# Sheet2.net
KiCad netlist of a schematic drawn in Altium Designer
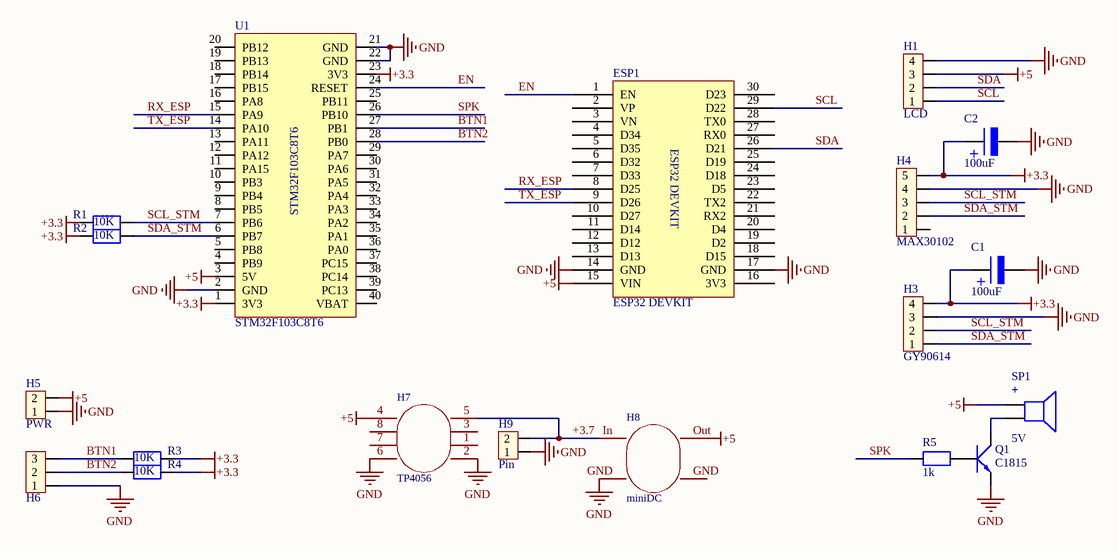
[diagram p0: Sheet2.SchDoc]

(export (version "E")
  (design (tool "Eeschema 10.0.6"))
  (components
    (comp (ref "C1")
      (value "100uF")
      (footprint "cap - 470uF/35v")
      (description "phan cuc")
      (libsource (lib "Scorer_Tran_Library") (part "Cap1"))
    )
    (comp (ref "C2")
      (value "100uF")
      (footprint "cap - 470uF/35v")
      (description "phan cuc")
      (libsource (lib "Scorer_Tran_Library") (part "Cap1"))
    )
    (comp (ref "ESP1")
      (value "ESP32 DEVKIT")
      (footprint "ESP32")
      (description "module")
      (libsource (lib "Scorer_Tran_Library") (part "ESP32"))
    )
    (comp (ref "H1")
      (value "LCD")
      (footprint "XH2.54 4P")
      (description "Header")
      (libsource (lib "SE_Altium_LIB") (part "HEADER 4P"))
    )
    (comp (ref "H3")
      (value "GY90614")
      (footprint "XH2.54 4P")
      (description "Header")
      (libsource (lib "SE_Altium_LIB") (part "HEADER 4P"))
    )
    (comp (ref "H4")
      (value "MAX30102")
      (footprint "XH2.54 5P")
      (description "Header")
      (libsource (lib "SE_Altium_LIB") (part "HEADER 5P"))
    )
    (comp (ref "H5")
      (value "PWR")
      (footprint "KF301 2P")
      (description "Header")
      (libsource (lib "SE_Altium_LIB") (part "HEADER 2P"))
    )
    (comp (ref "H6")
      (value "KF301")
      (footprint "KF301 3P")
      (description "Header")
      (libsource (lib "SE_Altium_LIB") (part "HEADER 3P"))
    )
    (comp (ref "H7")
      (value "TP4056")
      (footprint "HDR2X4")
      (fields (field (name "PUBLISHER") "Altium Limited"))
      (libsource (lib "") (part "root_0_Header 4X2__1"))
    )
    (comp (ref "H8")
      (value "miniDC")
      (footprint "HDR2X4")
      (fields (field (name "PUBLISHER") "Altium Limited"))
      (libsource (lib "altium-import") (part "root_0_Header 4X2_"))
    )
    (comp (ref "H9")
      (value "Pin")
      (footprint "KF301 2P")
      (description "Header")
      (libsource (lib "SE_Altium_LIB") (part "HEADER 2P"))
    )
    (comp (ref "Q1")
      (value "C1815")
      (footprint "NPN")
      (description "NPN")
      (libsource (lib "Scorer_Tran_Library") (part "C1815"))
    )
    (comp (ref "R1")
      (value "10K")
      (footprint "RES")
      (description "1k, 1/4W")
      (libsource (lib "Scorer_Tran_Library") (part "Resistor"))
    )
    (comp (ref "R2")
      (value "10K")
      (footprint "RES")
      (description "1k, 1/4W")
      (libsource (lib "Scorer_Tran_Library") (part "Resistor"))
    )
    (comp (ref "R3")
      (value "10K")
      (footprint "RES")
      (description "1k, 1/4W")
      (libsource (lib "Scorer_Tran_Library") (part "Resistor"))
    )
    (comp (ref "R4")
      (value "10K")
      (footprint "RES")
      (description "1k, 1/4W")
      (libsource (lib "Scorer_Tran_Library") (part "Resistor"))
    )
    (comp (ref "R5")
      (value "1k")
      (footprint "RES")
      (description "1k, 1/4W")
      (libsource (lib "Scorer_Tran_Library") (part "Resistor"))
    )
    (comp (ref "SP1")
      (value "5V")
      (footprint "Coi chip 5V")
      (description "Speaker")
      (libsource (lib "Scorer_Tran_Library") (part "Coi chip 5V"))
    )
    (comp (ref "U1")
      (value "STM32F103C8T6")
      (footprint "KIT STM32F103C8T6")
      (libsource (lib "Scorer_Tran_Library") (part "STM32"))
    )
  )
  (nets
    (net (code "1") (name "+3.3") (class "Default")
      (node (ref "C1") (pin "1") (pinfunction "VCC_1") (pintype "passive"))
      (node (ref "C2") (pin "1") (pinfunction "VCC_1") (pintype "passive"))
      (node (ref "H3") (pin "4") (pinfunction "4_4") (pintype "passive"))
      (node (ref "H4") (pin "5") (pinfunction "5_5") (pintype "passive"))
      (node (ref "R1") (pin "2") (pinfunction "2_2") (pintype "passive"))
      (node (ref "R2") (pin "2") (pinfunction "2_2") (pintype "passive"))
      (node (ref "R3") (pin "1") (pinfunction "1_1") (pintype "passive"))
      (node (ref "R4") (pin "1") (pinfunction "1_1") (pintype "passive"))
      (node (ref "U1") (pin "1") (pinfunction "3V3_1") (pintype "passive"))
      (node (ref "U1") (pin "23") (pinfunction "3V3_23") (pintype "passive"))
    )
    (net (code "2") (name "+5") (class "Default")
      (node (ref "ESP1") (pin "15") (pinfunction "VIN_15") (pintype "passive"))
      (node (ref "H1") (pin "3") (pinfunction "3_3") (pintype "passive"))
      (node (ref "H5") (pin "2") (pinfunction "2_2") (pintype "passive"))
      (node (ref "H7") (pin "4") (pinfunction "1_4") (pintype "passive"))
      (node (ref "H8") (pin "Out") (pinfunction "2_Out") (pintype "passive"))
      (node (ref "SP1") (pin "1") (pinfunction "1_1") (pintype "passive"))
      (node (ref "U1") (pin "3") (pinfunction "5V_3") (pintype "passive"))
    )
    (net (code "3") (name "/+3.7") (class "Default")
      (node (ref "H7") (pin "5") (pinfunction "2_5") (pintype "passive"))
      (node (ref "H8") (pin "In") (pinfunction "1_In") (pintype "passive"))
      (node (ref "H9") (pin "2") (pinfunction "2_2") (pintype "passive"))
    )
    (net (code "4") (name "/BTN1") (class "Default")
      (node (ref "H6") (pin "3") (pinfunction "3_3") (pintype "passive"))
      (node (ref "R3") (pin "2") (pinfunction "2_2") (pintype "passive"))
      (node (ref "U1") (pin "27") (pinfunction "PB1_27") (pintype "passive"))
    )
    (net (code "5") (name "/BTN2") (class "Default")
      (node (ref "H6") (pin "2") (pinfunction "2_2") (pintype "passive"))
      (node (ref "R4") (pin "2") (pinfunction "2_2") (pintype "passive"))
      (node (ref "U1") (pin "28") (pinfunction "PB0_28") (pintype "passive"))
    )
    (net (code "6") (name "/EN") (class "Default")
      (node (ref "ESP1") (pin "1") (pinfunction "EN_1") (pintype "passive"))
      (node (ref "U1") (pin "24") (pinfunction "RESET_24") (pintype "passive"))
    )
    (net (code "7") (name "/RX_ESP") (class "Default")
      (node (ref "ESP1") (pin "8") (pinfunction "D25_8") (pintype "passive"))
      (node (ref "U1") (pin "15") (pinfunction "PA9_15") (pintype "passive"))
    )
    (net (code "8") (name "/SCL") (class "Default")
      (node (ref "ESP1") (pin "29") (pinfunction "D22_29") (pintype "passive"))
      (node (ref "H1") (pin "1") (pinfunction "1_1") (pintype "passive"))
    )
    (net (code "9") (name "/SCL_STM") (class "Default")
      (node (ref "H3") (pin "2") (pinfunction "2_2") (pintype "passive"))
      (node (ref "H4") (pin "3") (pinfunction "3_3") (pintype "passive"))
      (node (ref "R1") (pin "1") (pinfunction "1_1") (pintype "passive"))
      (node (ref "U1") (pin "7") (pinfunction "PB6_7") (pintype "passive"))
    )
    (net (code "10") (name "/SDA") (class "Default")
      (node (ref "ESP1") (pin "26") (pinfunction "D21_26") (pintype "passive"))
      (node (ref "H1") (pin "2") (pinfunction "2_2") (pintype "passive"))
    )
    (net (code "11") (name "/SDA_STM") (class "Default")
      (node (ref "H3") (pin "1") (pinfunction "1_1") (pintype "passive"))
      (node (ref "H4") (pin "2") (pinfunction "2_2") (pintype "passive"))
      (node (ref "R2") (pin "1") (pinfunction "1_1") (pintype "passive"))
      (node (ref "U1") (pin "6") (pinfunction "PB7_6") (pintype "passive"))
    )
    (net (code "12") (name "/SPK") (class "Default")
      (node (ref "R5") (pin "2") (pinfunction "2_2") (pintype "passive"))
      (node (ref "U1") (pin "26") (pinfunction "PB10_26") (pintype "passive"))
    )
    (net (code "13") (name "/TX_ESP") (class "Default")
      (node (ref "ESP1") (pin "9") (pinfunction "D26_9") (pintype "passive"))
      (node (ref "U1") (pin "14") (pinfunction "PA10_14") (pintype "passive"))
    )
    (net (code "14") (name "GND") (class "Default")
      (node (ref "C1") (pin "2") (pinfunction "GND_2") (pintype "passive"))
      (node (ref "C2") (pin "2") (pinfunction "GND_2") (pintype "passive"))
      (node (ref "ESP1") (pin "14") (pinfunction "GND_14") (pintype "passive"))
      (node (ref "ESP1") (pin "17") (pinfunction "GND_17") (pintype "passive"))
      (node (ref "H1") (pin "4") (pinfunction "4_4") (pintype "passive"))
      (node (ref "H3") (pin "3") (pinfunction "3_3") (pintype "passive"))
      (node (ref "H4") (pin "4") (pinfunction "4_4") (pintype "passive"))
      (node (ref "H5") (pin "1") (pinfunction "1_1") (pintype "passive"))
      (node (ref "H6") (pin "1") (pinfunction "1_1") (pintype "passive"))
      (node (ref "H7") (pin "2") (pinfunction "8_2") (pintype "passive"))
      (node (ref "H7") (pin "6") (pinfunction "7_6") (pintype "passive"))
      (node (ref "H8") (pin "GND") (pinfunction "7_GND") (pintype "passive"))
      (node (ref "H9") (pin "1") (pinfunction "1_1") (pintype "passive"))
      (node (ref "Q1") (pin "1") (pinfunction "E_1") (pintype "passive"))
      (node (ref "U1") (pin "2") (pinfunction "GND_2") (pintype "passive"))
      (node (ref "U1") (pin "21") (pinfunction "GND_21") (pintype "passive"))
      (node (ref "U1") (pin "22") (pinfunction "GND_22") (pintype "passive"))
    )
    (net (code "15") (name "Net-(Q1-B)") (class "Default")
      (node (ref "Q1") (pin "3") (pinfunction "B_3") (pintype "passive"))
      (node (ref "R5") (pin "1") (pinfunction "1_1") (pintype "passive"))
    )
    (net (code "16") (name "Net-(Q1-C)") (class "Default")
      (node (ref "Q1") (pin "2") (pinfunction "C_2") (pintype "passive"))
      (node (ref "SP1") (pin "2") (pinfunction "2_2") (pintype "passive"))
    )
    (net (code "17") (name "unconnected-(ESP1-3V3-Pad16)") (class "Default")
      (node (ref "ESP1") (pin "16") (pinfunction "3V3_16") (pintype "passive"))
    )
    (net (code "18") (name "unconnected-(ESP1-D2-Pad19)") (class "Default")
      (node (ref "ESP1") (pin "19") (pinfunction "D2_19") (pintype "passive"))
    )
    (net (code "19") (name "unconnected-(ESP1-D4-Pad20)") (class "Default")
      (node (ref "ESP1") (pin "20") (pinfunction "D4_20") (pintype "passive"))
    )
    (net (code "20") (name "unconnected-(ESP1-D5-Pad23)") (class "Default")
      (node (ref "ESP1") (pin "23") (pinfunction "D5_23") (pintype "passive"))
    )
    (net (code "21") (name "unconnected-(ESP1-D12-Pad12)") (class "Default")
      (node (ref "ESP1") (pin "12") (pinfunction "D12_12") (pintype "passive"))
    )
    (net (code "22") (name "unconnected-(ESP1-D13-Pad13)") (class "Default")
      (node (ref "ESP1") (pin "13") (pinfunction "D13_13") (pintype "passive"))
    )
    (net (code "23") (name "unconnected-(ESP1-D14-Pad11)") (class "Default")
      (node (ref "ESP1") (pin "11") (pinfunction "D14_11") (pintype "passive"))
    )
    (net (code "24") (name "unconnected-(ESP1-D15-Pad18)") (class "Default")
      (node (ref "ESP1") (pin "18") (pinfunction "D15_18") (pintype "passive"))
    )
    (net (code "25") (name "unconnected-(ESP1-D18-Pad24)") (class "Default")
      (node (ref "ESP1") (pin "24") (pinfunction "D18_24") (pintype "passive"))
    )
    (net (code "26") (name "unconnected-(ESP1-D19-Pad25)") (class "Default")
      (node (ref "ESP1") (pin "25") (pinfunction "D19_25") (pintype "passive"))
    )
    (net (code "27") (name "unconnected-(ESP1-D23-Pad30)") (class "Default")
      (node (ref "ESP1") (pin "30") (pinfunction "D23_30") (pintype "passive"))
    )
    (net (code "28") (name "unconnected-(ESP1-D27-Pad10)") (class "Default")
      (node (ref "ESP1") (pin "10") (pinfunction "D27_10") (pintype "passive"))
    )
    (net (code "29") (name "unconnected-(ESP1-D32-Pad6)") (class "Default")
      (node (ref "ESP1") (pin "6") (pinfunction "D32_6") (pintype "passive"))
    )
    (net (code "30") (name "unconnected-(ESP1-D33-Pad7)") (class "Default")
      (node (ref "ESP1") (pin "7") (pinfunction "D33_7") (pintype "passive"))
    )
    (net (code "31") (name "unconnected-(ESP1-D34-Pad4)") (class "Default")
      (node (ref "ESP1") (pin "4") (pinfunction "D34_4") (pintype "passive"))
    )
    (net (code "32") (name "unconnected-(ESP1-D35-Pad5)") (class "Default")
      (node (ref "ESP1") (pin "5") (pinfunction "D35_5") (pintype "passive"))
    )
    (net (code "33") (name "unconnected-(ESP1-RX0-Pad27)") (class "Default")
      (node (ref "ESP1") (pin "27") (pinfunction "RX0_27") (pintype "passive"))
    )
    (net (code "34") (name "unconnected-(ESP1-RX2-Pad21)") (class "Default")
      (node (ref "ESP1") (pin "21") (pinfunction "RX2_21") (pintype "passive"))
    )
    (net (code "35") (name "unconnected-(ESP1-TX0-Pad28)") (class "Default")
      (node (ref "ESP1") (pin "28") (pinfunction "TX0_28") (pintype "passive"))
    )
    (net (code "36") (name "unconnected-(ESP1-TX2-Pad22)") (class "Default")
      (node (ref "ESP1") (pin "22") (pinfunction "TX2_22") (pintype "passive"))
    )
    (net (code "37") (name "unconnected-(ESP1-VN-Pad3)") (class "Default")
      (node (ref "ESP1") (pin "3") (pinfunction "VN_3") (pintype "passive"))
    )
    (net (code "38") (name "unconnected-(ESP1-VP-Pad2)") (class "Default")
      (node (ref "ESP1") (pin "2") (pinfunction "VP_2") (pintype "passive"))
    )
    (net (code "39") (name "unconnected-(H4-Pad1)") (class "Default")
      (node (ref "H4") (pin "1") (pinfunction "1_1") (pintype "passive"))
    )
    (net (code "40") (name "unconnected-(H7-3-Pad8)") (class "Default")
      (node (ref "H7") (pin "8") (pinfunction "3_8") (pintype "passive"))
    )
    (net (code "41") (name "unconnected-(H7-4-Pad3)") (class "Default")
      (node (ref "H7") (pin "3") (pinfunction "4_3") (pintype "passive"))
    )
    (net (code "42") (name "unconnected-(H7-5-Pad7)") (class "Default")
      (node (ref "H7") (pin "7") (pinfunction "5_7") (pintype "passive"))
    )
    (net (code "43") (name "unconnected-(H7-6-Pad1)") (class "Default")
      (node (ref "H7") (pin "1") (pinfunction "6_1") (pintype "passive"))
    )
    (net (code "44") (name "unconnected-(H8-8-PadGND)") (class "Default")
      (node (ref "H8") (pin "GND") (pinfunction "8_GND") (pintype "passive"))
    )
    (net (code "45") (name "unconnected-(U1-PA0-Pad36)") (class "Default")
      (node (ref "U1") (pin "36") (pinfunction "PA0_36") (pintype "passive"))
    )
    (net (code "46") (name "unconnected-(U1-PA1-Pad35)") (class "Default")
      (node (ref "U1") (pin "35") (pinfunction "PA1_35") (pintype "passive"))
    )
    (net (code "47") (name "unconnected-(U1-PA2-Pad34)") (class "Default")
      (node (ref "U1") (pin "34") (pinfunction "PA2_34") (pintype "passive"))
    )
    (net (code "48") (name "unconnected-(U1-PA3-Pad33)") (class "Default")
      (node (ref "U1") (pin "33") (pinfunction "PA3_33") (pintype "passive"))
    )
    (net (code "49") (name "unconnected-(U1-PA4-Pad32)") (class "Default")
      (node (ref "U1") (pin "32") (pinfunction "PA4_32") (pintype "passive"))
    )
    (net (code "50") (name "unconnected-(U1-PA5-Pad31)") (class "Default")
      (node (ref "U1") (pin "31") (pinfunction "PA5_31") (pintype "passive"))
    )
    (net (code "51") (name "unconnected-(U1-PA6-Pad30)") (class "Default")
      (node (ref "U1") (pin "30") (pinfunction "PA6_30") (pintype "passive"))
    )
    (net (code "52") (name "unconnected-(U1-PA7-Pad29)") (class "Default")
      (node (ref "U1") (pin "29") (pinfunction "PA7_29") (pintype "passive"))
    )
    (net (code "53") (name "unconnected-(U1-PA8-Pad16)") (class "Default")
      (node (ref "U1") (pin "16") (pinfunction "PA8_16") (pintype "passive"))
    )
    (net (code "54") (name "unconnected-(U1-PA11-Pad13)") (class "Default")
      (node (ref "U1") (pin "13") (pinfunction "PA11_13") (pintype "passive"))
    )
    (net (code "55") (name "unconnected-(U1-PA12-Pad12)") (class "Default")
      (node (ref "U1") (pin "12") (pinfunction "PA12_12") (pintype "passive"))
    )
    (net (code "56") (name "unconnected-(U1-PA15-Pad11)") (class "Default")
      (node (ref "U1") (pin "11") (pinfunction "PA15_11") (pintype "passive"))
    )
    (net (code "57") (name "unconnected-(U1-PB3-Pad10)") (class "Default")
      (node (ref "U1") (pin "10") (pinfunction "PB3_10") (pintype "passive"))
    )
    (net (code "58") (name "unconnected-(U1-PB4-Pad9)") (class "Default")
      (node (ref "U1") (pin "9") (pinfunction "PB4_9") (pintype "passive"))
    )
    (net (code "59") (name "unconnected-(U1-PB5-Pad8)") (class "Default")
      (node (ref "U1") (pin "8") (pinfunction "PB5_8") (pintype "passive"))
    )
    (net (code "60") (name "unconnected-(U1-PB8-Pad5)") (class "Default")
      (node (ref "U1") (pin "5") (pinfunction "PB8_5") (pintype "passive"))
    )
    (net (code "61") (name "unconnected-(U1-PB9-Pad4)") (class "Default")
      (node (ref "U1") (pin "4") (pinfunction "PB9_4") (pintype "passive"))
    )
    (net (code "62") (name "unconnected-(U1-PB11-Pad25)") (class "Default")
      (node (ref "U1") (pin "25") (pinfunction "PB11_25") (pintype "passive"))
    )
    (net (code "63") (name "unconnected-(U1-PB12-Pad20)") (class "Default")
      (node (ref "U1") (pin "20") (pinfunction "PB12_20") (pintype "passive"))
    )
    (net (code "64") (name "unconnected-(U1-PB13-Pad19)") (class "Default")
      (node (ref "U1") (pin "19") (pinfunction "PB13_19") (pintype "passive"))
    )
    (net (code "65") (name "unconnected-(U1-PB14-Pad18)") (class "Default")
      (node (ref "U1") (pin "18") (pinfunction "PB14_18") (pintype "passive"))
    )
    (net (code "66") (name "unconnected-(U1-PB15-Pad17)") (class "Default")
      (node (ref "U1") (pin "17") (pinfunction "PB15_17") (pintype "passive"))
    )
    (net (code "67") (name "unconnected-(U1-PC13-Pad39)") (class "Default")
      (node (ref "U1") (pin "39") (pinfunction "PC13_39") (pintype "passive"))
    )
    (net (code "68") (name "unconnected-(U1-PC14-Pad38)") (class "Default")
      (node (ref "U1") (pin "38") (pinfunction "PC14_38") (pintype "passive"))
    )
    (net (code "69") (name "unconnected-(U1-PC15-Pad37)") (class "Default")
      (node (ref "U1") (pin "37") (pinfunction "PC15_37") (pintype "passive"))
    )
    (net (code "70") (name "unconnected-(U1-VBAT-Pad40)") (class "Default")
      (node (ref "U1") (pin "40") (pinfunction "VBAT_40") (pintype "passive"))
    )
  )
)
